# Rs232Iso-v1_2.net
KiCad netlist of a schematic drawn in EAGLE
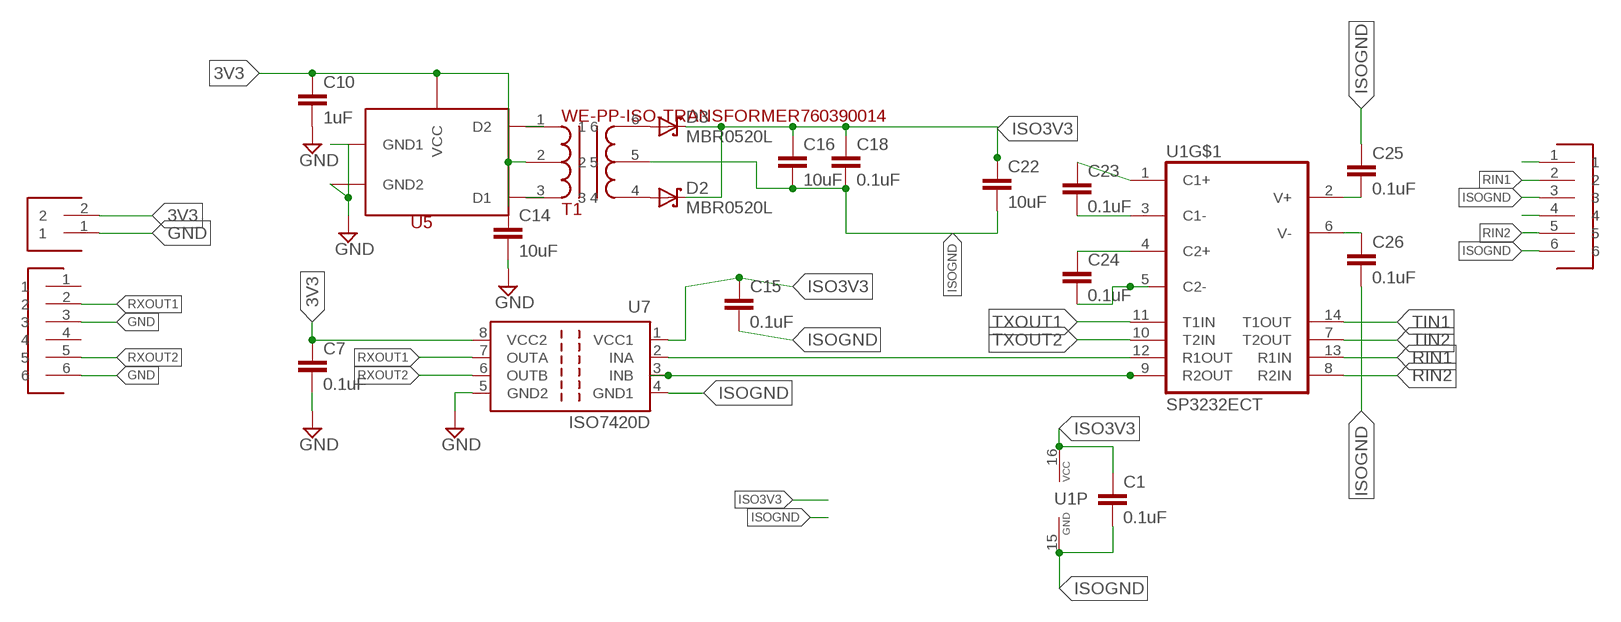
[diagram p0: schematic, sheet 1]

(export (version "E")
  (design (tool "Eeschema 10.0.6"))
  (components
    (comp (ref "C1")
      (value "0.1uF")
      (footprint "eagle-import:0603")
      (libsource (lib "eagle-import") (part "CAP0603"))
    )
    (comp (ref "C7")
      (value "0.1uF")
      (footprint "eagle-import:0603")
      (libsource (lib "eagle-import") (part "CAP0603"))
    )
    (comp (ref "C10")
      (value "1uF")
      (footprint "eagle-import:0805")
      (libsource (lib "eagle-import") (part "CAP0805"))
    )
    (comp (ref "C14")
      (value "10uF")
      (footprint "eagle-import:0805")
      (libsource (lib "eagle-import") (part "CAP0805"))
    )
    (comp (ref "C15")
      (value "0.1uF")
      (footprint "eagle-import:0603")
      (libsource (lib "eagle-import") (part "CAP0603"))
    )
    (comp (ref "C16")
      (value "10uF")
      (footprint "eagle-import:0805")
      (libsource (lib "eagle-import") (part "CAP0805"))
    )
    (comp (ref "C18")
      (value "0.1uF")
      (footprint "eagle-import:0603")
      (libsource (lib "eagle-import") (part "CAP0603"))
    )
    (comp (ref "C22")
      (value "10uF")
      (footprint "eagle-import:0805")
      (libsource (lib "eagle-import") (part "CAP0805"))
    )
    (comp (ref "C23")
      (value "0.1uF")
      (footprint "eagle-import:0603")
      (libsource (lib "eagle-import") (part "CAP0603"))
    )
    (comp (ref "C24")
      (value "0.1uF")
      (footprint "eagle-import:0603")
      (libsource (lib "eagle-import") (part "CAP0603"))
    )
    (comp (ref "C25")
      (value "0.1uF")
      (footprint "eagle-import:0603")
      (libsource (lib "eagle-import") (part "CAP0603"))
    )
    (comp (ref "C26")
      (value "0.1uF")
      (footprint "eagle-import:0603")
      (libsource (lib "eagle-import") (part "CAP0603"))
    )
    (comp (ref "D2")
      (value "MBR0520L")
      (footprint "eagle-import:SOD123")
      (libsource (lib "eagle-import") (part "MBR0520L"))
    )
    (comp (ref "D3")
      (value "MBR0520L")
      (footprint "eagle-import:SOD123")
      (libsource (lib "eagle-import") (part "MBR0520L"))
    )
    (comp (ref "J1")
      (value "CON-2STD-2.54")
      (footprint "eagle-import:CON-2")
      (libsource (lib "eagle-import") (part "CON-2STD-2.54"))
    )
    (comp (ref "J2")
      (value "CON-6")
      (footprint "eagle-import:CON-6")
      (libsource (lib "eagle-import") (part "CON-6"))
    )
    (comp (ref "J4")
      (value "CON-6")
      (footprint "eagle-import:CON-6")
      (libsource (lib "eagle-import") (part "CON-6"))
    )
    (comp (ref "T1")
      (value "WE-PP-ISO-TRANSFORMER760390014")
      (footprint "eagle-import:WE_TRANSFORMER")
      (libsource (lib "eagle-import") (part "WE-PP-ISO-TRANSFORMER760390014"))
    )
    (comp (ref "U1")
      (value "SP3232ECT")
      (footprint "eagle-import:SO16")
      (libsource (lib "eagle-import") (part "SP3232ECT"))
    )
    (comp (ref "U5")
      (value "SN6501DBVT")
      (footprint "eagle-import:SOT23-5L")
      (libsource (lib "eagle-import") (part "SN6501DBVT"))
    )
    (comp (ref "U7")
      (value "ISO7420D")
      (footprint "eagle-import:SO08")
      (libsource (lib "eagle-import") (part "ISO7420D"))
    )
  )
  (nets
    (net (code "1") (name "3V3") (class "Default")
      (node (ref "C10") (pin "1") (pinfunction "1_1") (pintype "passive"))
      (node (ref "C14") (pin "1") (pinfunction "1_1") (pintype "passive"))
      (node (ref "C7") (pin "1") (pinfunction "1_1") (pintype "passive"))
      (node (ref "J1") (pin "2") (pinfunction "2_2") (pintype "bidirectional"))
      (node (ref "T1") (pin "2") (pinfunction "2_2") (pintype "input"))
      (node (ref "U5") (pin "2") (pinfunction "VCC_2") (pintype "bidirectional"))
      (node (ref "U7") (pin "8") (pinfunction "VCC2_8") (pintype "power_in"))
    )
    (net (code "2") (name "GND") (class "Default")
      (node (ref "C10") (pin "2") (pinfunction "2_2") (pintype "passive"))
      (node (ref "C14") (pin "2") (pinfunction "2_2") (pintype "passive"))
      (node (ref "C7") (pin "2") (pinfunction "2_2") (pintype "passive"))
      (node (ref "J1") (pin "1") (pinfunction "1_1") (pintype "bidirectional"))
      (node (ref "J4") (pin "3") (pinfunction "3_3") (pintype "bidirectional"))
      (node (ref "J4") (pin "6") (pinfunction "6_6") (pintype "bidirectional"))
      (node (ref "U5") (pin "4") (pinfunction "GND1_4") (pintype "bidirectional"))
      (node (ref "U5") (pin "5") (pinfunction "GND2_5") (pintype "bidirectional"))
      (node (ref "U7") (pin "5") (pinfunction "GND2_5") (pintype "power_in"))
    )
    (net (code "3") (name "ISO3V3") (class "Default")
      (node (ref "C1") (pin "1") (pinfunction "1_1") (pintype "passive"))
      (node (ref "C15") (pin "1") (pinfunction "1_1") (pintype "passive"))
      (node (ref "C16") (pin "1") (pinfunction "1_1") (pintype "passive"))
      (node (ref "C18") (pin "1") (pinfunction "1_1") (pintype "passive"))
      (node (ref "C22") (pin "1") (pinfunction "1_1") (pintype "passive"))
      (node (ref "D2") (pin "C") (pinfunction "C_C") (pintype "passive"))
      (node (ref "D3") (pin "C") (pinfunction "C_C") (pintype "passive"))
      (node (ref "U1") (pin "16") (pinfunction "VCC_16") (pintype "power_in"))
      (node (ref "U7") (pin "1") (pinfunction "VCC1_1") (pintype "power_in"))
    )
    (net (code "4") (name "ISOGND") (class "Default")
      (node (ref "C1") (pin "2") (pinfunction "2_2") (pintype "passive"))
      (node (ref "C15") (pin "2") (pinfunction "2_2") (pintype "passive"))
      (node (ref "C16") (pin "2") (pinfunction "2_2") (pintype "passive"))
      (node (ref "C18") (pin "2") (pinfunction "2_2") (pintype "passive"))
      (node (ref "C22") (pin "2") (pinfunction "2_2") (pintype "passive"))
      (node (ref "C25") (pin "1") (pinfunction "1_1") (pintype "passive"))
      (node (ref "C26") (pin "2") (pinfunction "2_2") (pintype "passive"))
      (node (ref "J2") (pin "3") (pinfunction "3_3") (pintype "bidirectional"))
      (node (ref "J2") (pin "6") (pinfunction "6_6") (pintype "bidirectional"))
      (node (ref "T1") (pin "5") (pinfunction "5_5") (pintype "passive"))
      (node (ref "U1") (pin "15") (pinfunction "GND_15") (pintype "power_in"))
      (node (ref "U7") (pin "4") (pinfunction "GND1_4") (pintype "power_in"))
    )
    (net (code "5") (name "Net-(D2-PadA)") (class "Default")
      (node (ref "D2") (pin "A") (pinfunction "A_A") (pintype "passive"))
      (node (ref "T1") (pin "4") (pinfunction "4_4") (pintype "passive"))
    )
    (net (code "6") (name "Net-(D3-PadA)") (class "Default")
      (node (ref "D3") (pin "A") (pinfunction "A_A") (pintype "passive"))
      (node (ref "T1") (pin "6") (pinfunction "6_6") (pintype "passive"))
    )
    (net (code "7") (name "Net-(U1A-C1+)") (class "Default")
      (node (ref "C23") (pin "1") (pinfunction "1_1") (pintype "passive"))
      (node (ref "U1") (pin "1") (pinfunction "C1+_1") (pintype "bidirectional"))
    )
    (net (code "8") (name "Net-(U1A-C1-)") (class "Default")
      (node (ref "C23") (pin "2") (pinfunction "2_2") (pintype "passive"))
      (node (ref "U1") (pin "3") (pinfunction "C1-_3") (pintype "bidirectional"))
    )
    (net (code "9") (name "Net-(U1A-C2+)") (class "Default")
      (node (ref "C24") (pin "1") (pinfunction "1_1") (pintype "passive"))
      (node (ref "U1") (pin "4") (pinfunction "C2+_4") (pintype "bidirectional"))
    )
    (net (code "10") (name "Net-(U1A-C2-)") (class "Default")
      (node (ref "C24") (pin "2") (pinfunction "2_2") (pintype "passive"))
      (node (ref "U1") (pin "5") (pinfunction "C2-_5") (pintype "bidirectional"))
    )
    (net (code "11") (name "Net-(U1A-R1OUT)") (class "Default")
      (node (ref "U1") (pin "12") (pinfunction "R1OUT_12") (pintype "output"))
      (node (ref "U7") (pin "2") (pinfunction "INA_2") (pintype "input"))
    )
    (net (code "12") (name "Net-(U1A-R2OUT)") (class "Default")
      (node (ref "U1") (pin "9") (pinfunction "R2OUT_9") (pintype "output"))
      (node (ref "U7") (pin "3") (pinfunction "INB_3") (pintype "input"))
    )
    (net (code "13") (name "Net-(U1A-V+)") (class "Default")
      (node (ref "C25") (pin "2") (pinfunction "2_2") (pintype "passive"))
      (node (ref "U1") (pin "2") (pinfunction "V+_2") (pintype "bidirectional"))
    )
    (net (code "14") (name "Net-(U1A-V-)") (class "Default")
      (node (ref "C26") (pin "1") (pinfunction "1_1") (pintype "passive"))
      (node (ref "U1") (pin "6") (pinfunction "V-_6") (pintype "bidirectional"))
    )
    (net (code "15") (name "Net-(U5-D1)") (class "Default")
      (node (ref "T1") (pin "3") (pinfunction "3_3") (pintype "input"))
      (node (ref "U5") (pin "1") (pinfunction "D1_1") (pintype "bidirectional"))
    )
    (net (code "16") (name "Net-(U5-D2)") (class "Default")
      (node (ref "T1") (pin "1") (pinfunction "1_1") (pintype "input"))
      (node (ref "U5") (pin "3") (pinfunction "D2_3") (pintype "bidirectional"))
    )
    (net (code "17") (name "RIN1") (class "Default")
      (node (ref "J2") (pin "2") (pinfunction "2_2") (pintype "bidirectional"))
      (node (ref "U1") (pin "13") (pinfunction "R1IN_13") (pintype "input"))
    )
    (net (code "18") (name "RIN2") (class "Default")
      (node (ref "J2") (pin "5") (pinfunction "5_5") (pintype "bidirectional"))
      (node (ref "U1") (pin "8") (pinfunction "R2IN_8") (pintype "input"))
    )
    (net (code "19") (name "RXOUT1") (class "Default")
      (node (ref "J4") (pin "2") (pinfunction "2_2") (pintype "bidirectional"))
      (node (ref "U7") (pin "7") (pinfunction "OUTA_7") (pintype "output"))
    )
    (net (code "20") (name "RXOUT2") (class "Default")
      (node (ref "J4") (pin "5") (pinfunction "5_5") (pintype "bidirectional"))
      (node (ref "U7") (pin "6") (pinfunction "OUTB_6") (pintype "output"))
    )
    (net (code "21") (name "TIN1") (class "Default")
      (node (ref "U1") (pin "14") (pinfunction "T1OUT_14") (pintype "output"))
    )
    (net (code "22") (name "TIN2") (class "Default")
      (node (ref "U1") (pin "7") (pinfunction "T2OUT_7") (pintype "output"))
    )
    (net (code "23") (name "TXOUT1") (class "Default")
      (node (ref "U1") (pin "11") (pinfunction "T1IN_11") (pintype "input"))
    )
    (net (code "24") (name "TXOUT2") (class "Default")
      (node (ref "U1") (pin "10") (pinfunction "T2IN_10") (pintype "input"))
    )
    (net (code "25") (name "unconnected-(J2-Pad1)") (class "Default")
      (node (ref "J2") (pin "1") (pinfunction "1_1") (pintype "bidirectional"))
    )
    (net (code "26") (name "unconnected-(J2-Pad4)") (class "Default")
      (node (ref "J2") (pin "4") (pinfunction "4_4") (pintype "bidirectional"))
    )
    (net (code "27") (name "unconnected-(J4-Pad1)") (class "Default")
      (node (ref "J4") (pin "1") (pinfunction "1_1") (pintype "bidirectional"))
    )
    (net (code "28") (name "unconnected-(J4-Pad4)") (class "Default")
      (node (ref "J4") (pin "4") (pinfunction "4_4") (pintype "bidirectional"))
    )
  )
)
